# pale_sieve.net
KiCad netlist of a schematic drawn in Altium Designer
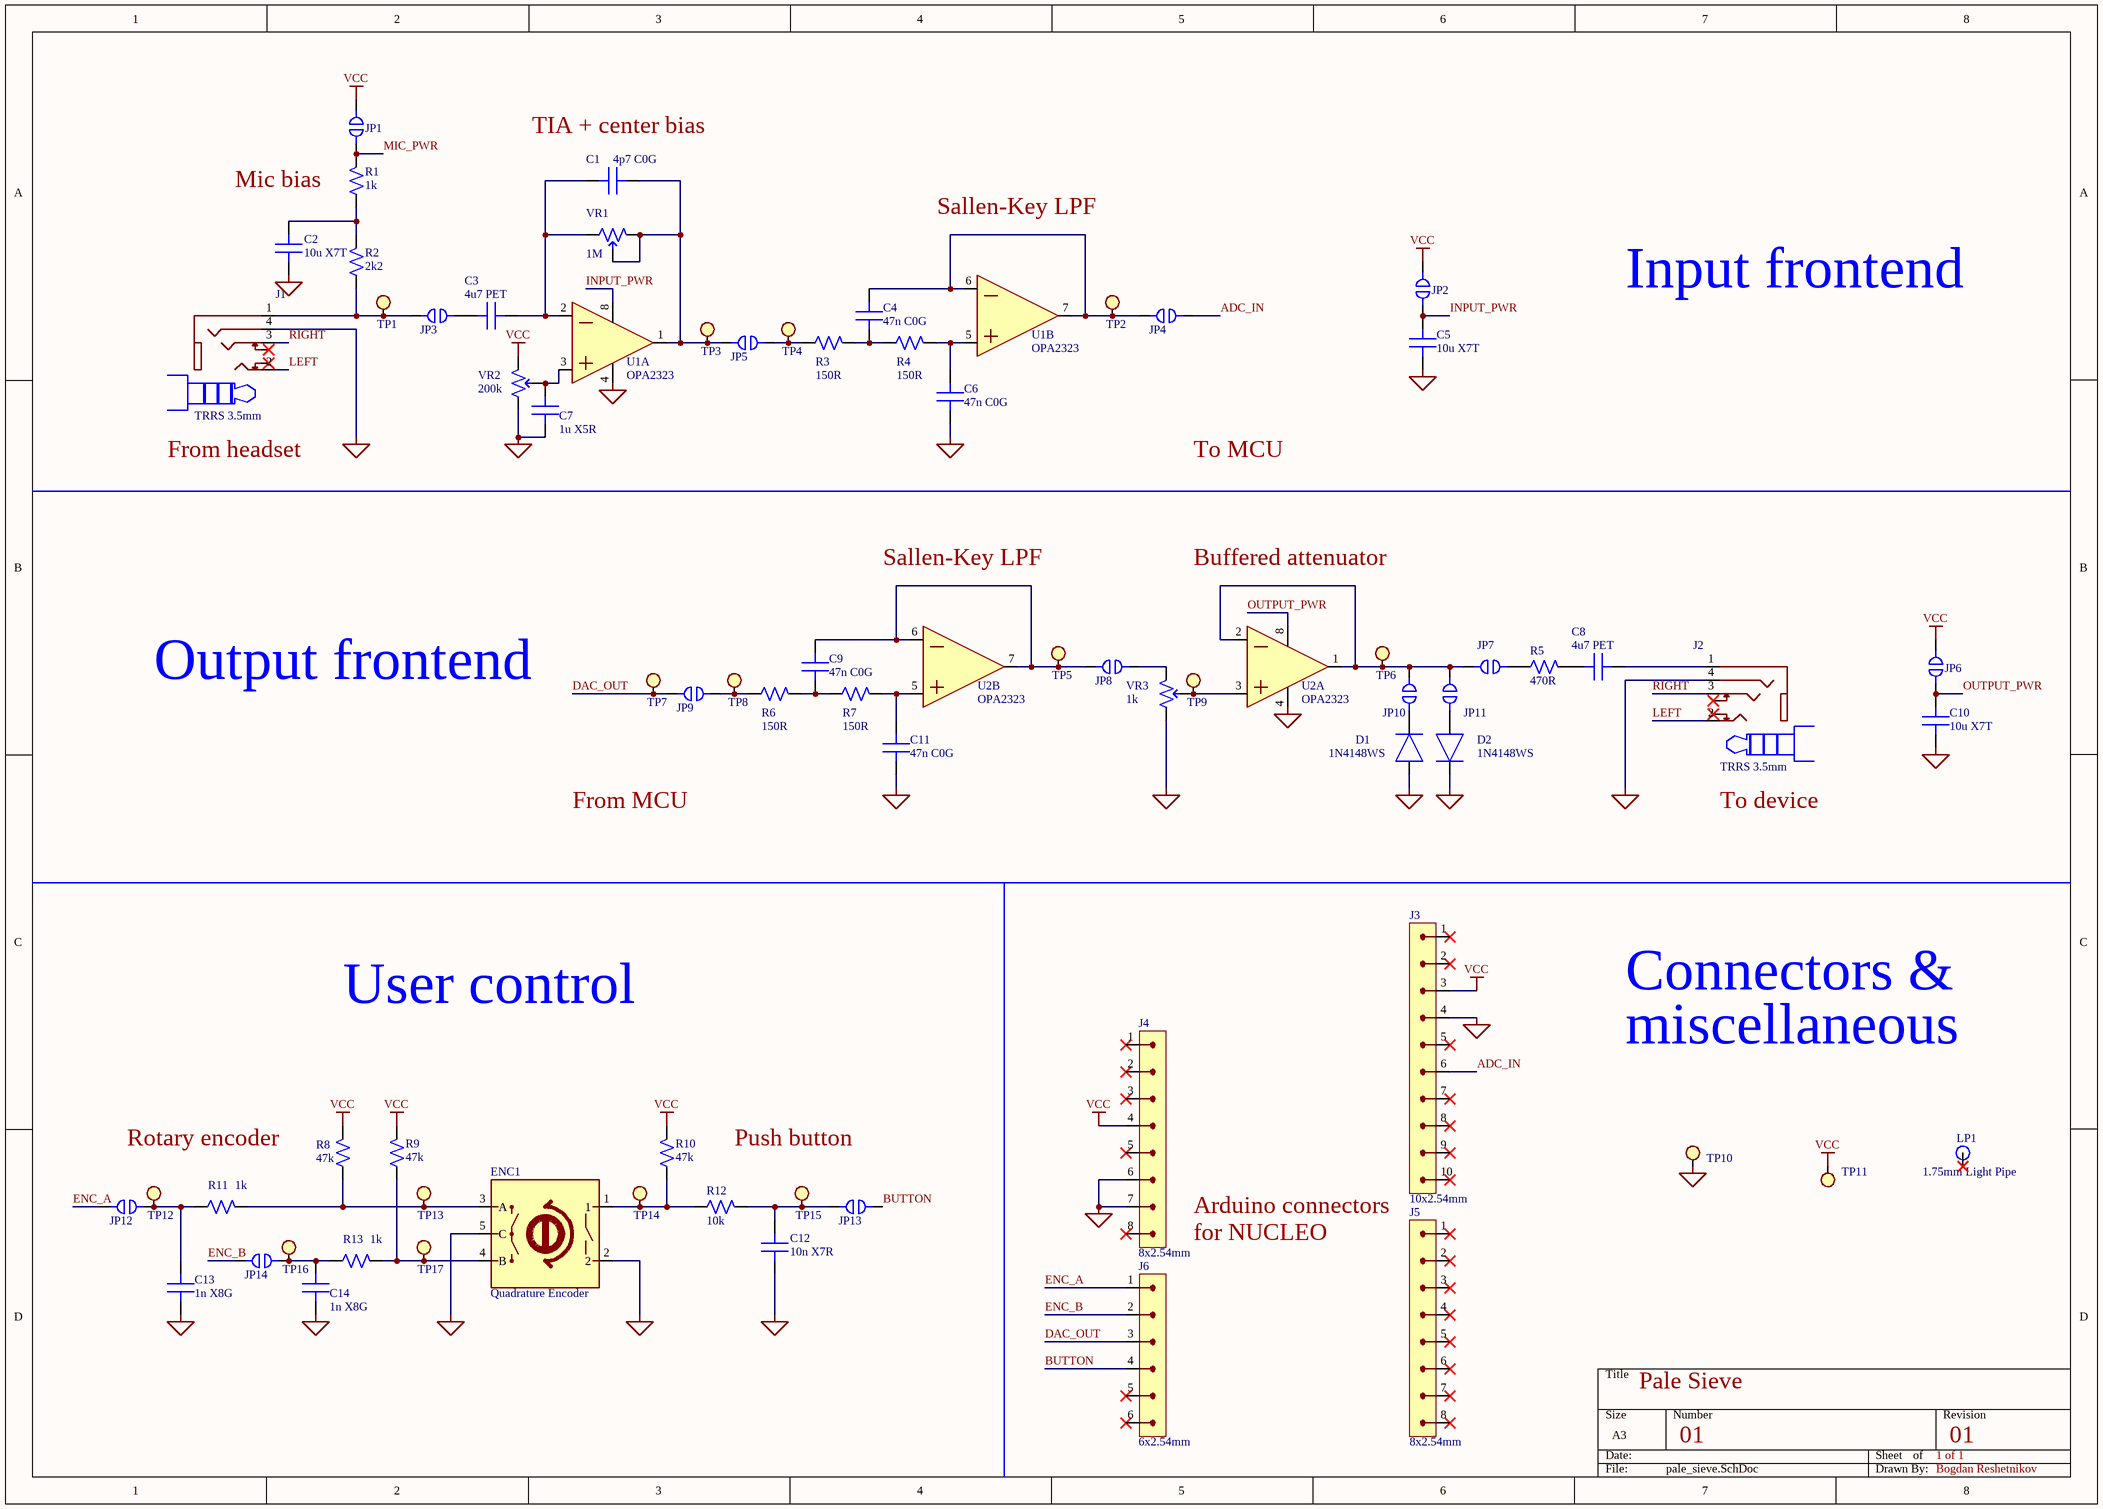
[diagram p0: pale_sieve.SchDoc]

(export (version "E")
  (design (tool "Eeschema 10.0.6"))
  (components
    (comp (ref "C1")
      (value "4p7 C0G")
      (footprint "C0603")
      (description "Multilayer Ceramic Capacitors MLCC - SMD/SMT 50V 4.7pF C0G 0603 5% Tol Ultra Low ESR")
      (fields
        (field (name "MANUFACTURER") "Kyocera AVX")
        (field (name "MANUFACTURER PART NUMBER") "06035U4R7JAT2A")
      )
      (libsource (lib "pale_sieve") (part "06035U4R7JAT2A"))
    )
    (comp (ref "C2")
      (value "10u X7T")
      (footprint "C0603")
      (fields
        (field (name "MANUFACTURER") "TDK")
        (field (name "MANUFACTURER PART NUMBER") "CGA3EDX7T1A106M080AU")
      )
      (libsource (lib "pale_sieve") (part "CGA3EDX7T1A106M080AU"))
    )
    (comp (ref "C3")
      (value "4u7 PET")
      (footprint "6054 WIMA")
      (description "Film Capacitor, Polyethylene Terephthalate, 100V, 10% +Tol, 10% -Tol, 4.7uF, Surface Mount, 6054")
      (fields
        (field (name "MANUFACTURER") "WIMA")
        (field (name "MANUFACTURER PART NUMBER") "SMDTD04470YA00KS00")
      )
      (libsource (lib "pale_sieve") (part "SMDTD04470YA00KS00"))
    )
    (comp (ref "C4")
      (value "47n C0G")
      (footprint "C0805")
      (fields
        (field (name "MANUFACTURER") "KEMET")
        (field (name "MANUFACTURER PART NUMBER") "C0805C473G3GECAUTO")
      )
      (libsource (lib "pale_sieve") (part "C0805C473G3GECAUTO"))
    )
    (comp (ref "C5")
      (value "10u X7T")
      (footprint "C0603")
      (fields
        (field (name "MANUFACTURER") "TDK")
        (field (name "MANUFACTURER PART NUMBER") "CGA3EDX7T1A106M080AU")
      )
      (libsource (lib "pale_sieve") (part "CGA3EDX7T1A106M080AU"))
    )
    (comp (ref "C6")
      (value "47n C0G")
      (footprint "C0805")
      (fields
        (field (name "MANUFACTURER") "KEMET")
        (field (name "MANUFACTURER PART NUMBER") "C0805C473G3GECAUTO")
      )
      (libsource (lib "pale_sieve") (part "C0805C473G3GECAUTO"))
    )
    (comp (ref "C7")
      (value "1u X5R")
      (footprint "C0603")
      (fields
        (field (name "MANUFACTURER") "Kyocera AVX")
        (field (name "MANUFACTURER PART NUMBER") "0603YD105KAT2A")
      )
      (libsource (lib "pale_sieve") (part "0603YD105KAT2A"))
    )
    (comp (ref "C8")
      (value "4u7 PET")
      (footprint "6054 WIMA")
      (description "Film Capacitor, Polyethylene Terephthalate, 100V, 10% +Tol, 10% -Tol, 4.7uF, Surface Mount, 6054")
      (fields
        (field (name "MANUFACTURER") "WIMA")
        (field (name "MANUFACTURER PART NUMBER") "SMDTD04470YA00KS00")
      )
      (libsource (lib "pale_sieve") (part "SMDTD04470YA00KS00"))
    )
    (comp (ref "C9")
      (value "47n C0G")
      (footprint "C0805")
      (fields
        (field (name "MANUFACTURER") "KEMET")
        (field (name "MANUFACTURER PART NUMBER") "C0805C473G3GECAUTO")
      )
      (libsource (lib "pale_sieve") (part "C0805C473G3GECAUTO"))
    )
    (comp (ref "C10")
      (value "10u X7T")
      (footprint "C0603")
      (fields
        (field (name "MANUFACTURER") "TDK")
        (field (name "MANUFACTURER PART NUMBER") "CGA3EDX7T1A106M080AU")
      )
      (libsource (lib "pale_sieve") (part "CGA3EDX7T1A106M080AU"))
    )
    (comp (ref "C11")
      (value "47n C0G")
      (footprint "C0805")
      (fields
        (field (name "MANUFACTURER") "KEMET")
        (field (name "MANUFACTURER PART NUMBER") "C0805C473G3GECAUTO")
      )
      (libsource (lib "pale_sieve") (part "C0805C473G3GECAUTO"))
    )
    (comp (ref "C12")
      (value "10n X7R")
      (footprint "C0603")
      (fields
        (field (name "MANUFACTURER") "Murata")
        (field (name "MANUFACTURER PART NUMBER") "GCM188R71H103KA37J")
      )
      (libsource (lib "pale_sieve") (part "GCM188R71H103KA37J"))
    )
    (comp (ref "C13")
      (value "1n X8G")
      (footprint "C0603")
      (fields
        (field (name "MANUFACTURER") "KEMET")
        (field (name "MANUFACTURER PART NUMBER") "C0603C102J2TACAUTO")
      )
      (libsource (lib "pale_sieve") (part "C0603C102J2TACAUTO"))
    )
    (comp (ref "C14")
      (value "1n X8G")
      (footprint "C0603")
      (fields
        (field (name "MANUFACTURER") "KEMET")
        (field (name "MANUFACTURER PART NUMBER") "C0603C102J2TACAUTO")
      )
      (libsource (lib "pale_sieve") (part "C0603C102J2TACAUTO"))
    )
    (comp (ref "D1")
      (value "1N4148WS")
      (footprint "SOD-323")
      (description "Rectifier Diode, 1 Phase, 1 Element, 0.15A, 100V V(RRM), Silicon")
      (fields (field (name "MANUFACTURER") "ON Semiconductor / Fairchild"))
      (libsource (lib "pale_sieve") (part "1N4148WS"))
    )
    (comp (ref "D2")
      (value "1N4148WS")
      (footprint "SOD-323")
      (description "Rectifier Diode, 1 Phase, 1 Element, 0.15A, 100V V(RRM), Silicon")
      (fields (field (name "MANUFACTURER") "ON Semiconductor / Fairchild"))
      (libsource (lib "pale_sieve") (part "1N4148WS"))
    )
    (comp (ref "ENC1")
      (value "Quadrature Encoder")
      (footprint "PEC11L")
      (description "Rotary Position Encoder")
      (fields
        (field (name "MANUFACTURER") "Bourns")
        (field (name "MANUFACTURER PART NUMBER") "PEC11L-4120F-S0020")
      )
      (libsource (lib "pale_sieve") (part "PEC11L-4120F-S0020"))
    )
    (comp (ref "J1")
      (value "TRRS 3.5mm")
      (footprint "SJ2-35894B-SMT")
      (description "3.5 mm, Stereo, Right Angle, Surface Mount (SMT), Audio Jack Connector")
      (fields
        (field (name "MANUFACTURER") "Same Sky")
        (field (name "MANUFACTURER PART NUMBER") "SJ2-35894B-SMT-TR")
      )
      (libsource (lib "") (part "SJ2-35894B-SMT-TR_1"))
    )
    (comp (ref "J2")
      (value "TRRS 3.5mm")
      (footprint "SJ2-35894B-SMT")
      (description "3.5 mm, Stereo, Right Angle, Surface Mount (SMT), Audio Jack Connector")
      (fields
        (field (name "MANUFACTURER") "Same Sky")
        (field (name "MANUFACTURER PART NUMBER") "SJ2-35894B-SMT-TR")
      )
      (libsource (lib "pale_sieve") (part "SJ2-35894B-SMT-TR"))
    )
    (comp (ref "J3")
      (value "10x2.54mm")
      (footprint "1X10 2.54MM")
      (libsource (lib "pale_sieve") (part "10x2.54mm"))
    )
    (comp (ref "J4") (value "8x2.54mm") (footprint "1x8 2.54MM") (libsource (lib "") (part "8x2.54mm_1")))
    (comp (ref "J5")
      (value "8x2.54mm")
      (footprint "1x8 2.54MM")
      (libsource (lib "pale_sieve") (part "8x2.54mm"))
    )
    (comp (ref "J6")
      (value "6x2.54mm")
      (footprint "1X6 2.54MM")
      (libsource (lib "pale_sieve") (part "6x2.54mm"))
    )
    (comp (ref "JP1")
      (value "Normally open")
      (footprint "SB 1.0x1.5mm")
      (libsource (lib "pale_sieve") (part "SolderBridge"))
    )
    (comp (ref "JP2")
      (value "Normally open")
      (footprint "SB 1.0x1.5mm")
      (libsource (lib "pale_sieve") (part "SolderBridge"))
    )
    (comp (ref "JP3")
      (value "Normally open")
      (footprint "SB 1.0x1.5mm")
      (libsource (lib "pale_sieve") (part "SolderBridge"))
    )
    (comp (ref "JP4")
      (value "Normally open")
      (footprint "SB 1.0x1.5mm")
      (libsource (lib "pale_sieve") (part "SolderBridge"))
    )
    (comp (ref "JP5")
      (value "Normally open")
      (footprint "SB 1.0x1.5mm")
      (libsource (lib "pale_sieve") (part "SolderBridge"))
    )
    (comp (ref "JP6")
      (value "Normally open")
      (footprint "SB 1.0x1.5mm")
      (libsource (lib "pale_sieve") (part "SolderBridge"))
    )
    (comp (ref "JP7")
      (value "Normally open")
      (footprint "SB 1.0x1.5mm")
      (libsource (lib "pale_sieve") (part "SolderBridge"))
    )
    (comp (ref "JP8")
      (value "Normally open")
      (footprint "SB 1.0x1.5mm")
      (libsource (lib "pale_sieve") (part "SolderBridge"))
    )
    (comp (ref "JP9")
      (value "Normally open")
      (footprint "SB 1.0x1.5mm")
      (libsource (lib "pale_sieve") (part "SolderBridge"))
    )
    (comp (ref "JP10")
      (value "Normally open")
      (footprint "SB 1.0x1.5mm")
      (libsource (lib "pale_sieve") (part "SolderBridge"))
    )
    (comp (ref "JP11")
      (value "Normally open")
      (footprint "SB 1.0x1.5mm")
      (libsource (lib "pale_sieve") (part "SolderBridge"))
    )
    (comp (ref "JP12")
      (value "Normally open")
      (footprint "SB 1.0x1.5mm")
      (libsource (lib "pale_sieve") (part "SolderBridge"))
    )
    (comp (ref "JP13")
      (value "Normally open")
      (footprint "SB 1.0x1.5mm")
      (libsource (lib "pale_sieve") (part "SolderBridge"))
    )
    (comp (ref "JP14")
      (value "Normally open")
      (footprint "SB 1.0x1.5mm")
      (libsource (lib "pale_sieve") (part "SolderBridge"))
    )
    (comp (ref "LP1")
      (value "1.75mm Light Pipe")
      (footprint "PTH 1.75MM")
      (libsource (lib "pale_sieve") (part "LightPipe"))
    )
    (comp (ref "R1")
      (value "1k")
      (footprint "R0603")
      (fields
        (field (name "MANUFACTURER") "Vishay")
        (field (name "MANUFACTURER PART NUMBER") "CRCW06031K00FKEI")
        (field (name "TOLERANCE") "1%")
      )
      (libsource (lib "pale_sieve") (part "CRCW06031K00FKEI"))
    )
    (comp (ref "R2")
      (value "2k2")
      (footprint "R0603")
      (fields
        (field (name "MANUFACTURER") "Vishay")
        (field (name "MANUFACTURER PART NUMBER") "CRCW06032K20FKEA")
        (field (name "TOLERANCE") "1%")
      )
      (libsource (lib "pale_sieve") (part "CRCW06032K20FKEA"))
    )
    (comp (ref "R3")
      (value "150R")
      (footprint "R0603")
      (fields
        (field (name "MANUFACTURER") "Vishay")
        (field (name "MANUFACTURER PART NUMBER") "CRCW0603150RFKEA")
        (field (name "TOLERANCE") "1%")
      )
      (libsource (lib "pale_sieve") (part "CRCW0603150RFKEA"))
    )
    (comp (ref "R4")
      (value "150R")
      (footprint "R0603")
      (fields
        (field (name "MANUFACTURER") "Vishay")
        (field (name "MANUFACTURER PART NUMBER") "CRCW0603150RFKEA")
        (field (name "TOLERANCE") "1%")
      )
      (libsource (lib "pale_sieve") (part "CRCW0603150RFKEA"))
    )
    (comp (ref "R5")
      (value "470R")
      (footprint "R0603")
      (fields
        (field (name "MANUFACTURER") "Vishay")
        (field (name "MANUFACTURER PART NUMBER") "CRCW0603470RFKEC")
        (field (name "TOLERANCE") "1%")
      )
      (libsource (lib "pale_sieve") (part "CRCW0603470RFKEC"))
    )
    (comp (ref "R6")
      (value "150R")
      (footprint "R0603")
      (fields
        (field (name "MANUFACTURER") "Vishay")
        (field (name "MANUFACTURER PART NUMBER") "CRCW0603150RFKEA")
        (field (name "TOLERANCE") "1%")
      )
      (libsource (lib "pale_sieve") (part "CRCW0603150RFKEA"))
    )
    (comp (ref "R7")
      (value "150R")
      (footprint "R0603")
      (fields
        (field (name "MANUFACTURER") "Vishay")
        (field (name "MANUFACTURER PART NUMBER") "CRCW0603150RFKEA")
        (field (name "TOLERANCE") "1%")
      )
      (libsource (lib "pale_sieve") (part "CRCW0603150RFKEA"))
    )
    (comp (ref "R8")
      (value "47k")
      (footprint "R0603")
      (fields
        (field (name "MANUFACTURER") "Vishay")
        (field (name "MANUFACTURER PART NUMBER") "CRCW060347K0FKEA")
        (field (name "TOLERANCE") "1%")
      )
      (libsource (lib "pale_sieve") (part "CRCW060347K0FKEA"))
    )
    (comp (ref "R9")
      (value "47k")
      (footprint "R0603")
      (fields
        (field (name "MANUFACTURER") "Vishay")
        (field (name "MANUFACTURER PART NUMBER") "CRCW060347K0FKEA")
        (field (name "TOLERANCE") "1%")
      )
      (libsource (lib "pale_sieve") (part "CRCW060347K0FKEA"))
    )
    (comp (ref "R10")
      (value "47k")
      (footprint "R0603")
      (fields
        (field (name "MANUFACTURER") "Vishay")
        (field (name "MANUFACTURER PART NUMBER") "CRCW060347K0FKEA")
        (field (name "TOLERANCE") "1%")
      )
      (libsource (lib "pale_sieve") (part "CRCW060347K0FKEA"))
    )
    (comp (ref "R11")
      (value "1k")
      (footprint "R0603")
      (fields
        (field (name "MANUFACTURER") "Vishay")
        (field (name "MANUFACTURER PART NUMBER") "CRCW06031K00FKEI")
        (field (name "TOLERANCE") "1%")
      )
      (libsource (lib "pale_sieve") (part "CRCW06031K00FKEI"))
    )
    (comp (ref "R12")
      (value "10k")
      (footprint "R0603")
      (fields
        (field (name "MANUFACTURER") "Vishay")
        (field (name "MANUFACTURER PART NUMBER") "CRCW060310K0FKEA")
        (field (name "TOLERANCE") "1%")
      )
      (libsource (lib "pale_sieve") (part "CRCW060310K0FKEA"))
    )
    (comp (ref "R13")
      (value "1k")
      (footprint "R0603")
      (fields
        (field (name "MANUFACTURER") "Vishay")
        (field (name "MANUFACTURER PART NUMBER") "CRCW06031K00FKEI")
        (field (name "TOLERANCE") "1%")
      )
      (libsource (lib "pale_sieve") (part "CRCW06031K00FKEI"))
    )
    (comp (ref "TP1")
      (value "PTH 0.75mm")
      (footprint "PTH 0.7MM")
      (libsource (lib "pale_sieve") (part "TestPoint"))
    )
    (comp (ref "TP2")
      (value "PTH 0.75mm")
      (footprint "PTH 0.7MM")
      (libsource (lib "pale_sieve") (part "TestPoint"))
    )
    (comp (ref "TP3")
      (value "PTH 0.75mm")
      (footprint "PTH 0.7MM")
      (libsource (lib "pale_sieve") (part "TestPoint"))
    )
    (comp (ref "TP4")
      (value "PTH 0.75mm")
      (footprint "PTH 0.7MM")
      (libsource (lib "pale_sieve") (part "TestPoint"))
    )
    (comp (ref "TP5")
      (value "PTH 0.75mm")
      (footprint "PTH 0.7MM")
      (libsource (lib "pale_sieve") (part "TestPoint"))
    )
    (comp (ref "TP6")
      (value "PTH 0.75mm")
      (footprint "PTH 0.7MM")
      (libsource (lib "pale_sieve") (part "TestPoint"))
    )
    (comp (ref "TP7")
      (value "PTH 0.75mm")
      (footprint "PTH 0.7MM")
      (libsource (lib "pale_sieve") (part "TestPoint"))
    )
    (comp (ref "TP8")
      (value "PTH 0.75mm")
      (footprint "PTH 0.7MM")
      (libsource (lib "pale_sieve") (part "TestPoint"))
    )
    (comp (ref "TP9")
      (value "PTH 0.75mm")
      (footprint "PTH 0.7MM")
      (libsource (lib "pale_sieve") (part "TestPoint"))
    )
    (comp (ref "TP10")
      (value "PTH 0.75mm")
      (footprint "PTH 0.7MM")
      (libsource (lib "pale_sieve") (part "TestPoint"))
    )
    (comp (ref "TP11")
      (value "PTH 0.75mm")
      (footprint "PTH 0.7MM")
      (libsource (lib "pale_sieve") (part "TestPoint"))
    )
    (comp (ref "TP12")
      (value "PTH 0.75mm")
      (footprint "PTH 0.7MM")
      (libsource (lib "pale_sieve") (part "TestPoint"))
    )
    (comp (ref "TP13")
      (value "PTH 0.75mm")
      (footprint "PTH 0.7MM")
      (libsource (lib "pale_sieve") (part "TestPoint"))
    )
    (comp (ref "TP14")
      (value "PTH 0.75mm")
      (footprint "PTH 0.7MM")
      (libsource (lib "pale_sieve") (part "TestPoint"))
    )
    (comp (ref "TP15")
      (value "PTH 0.75mm")
      (footprint "PTH 0.7MM")
      (libsource (lib "pale_sieve") (part "TestPoint"))
    )
    (comp (ref "TP16")
      (value "PTH 0.75mm")
      (footprint "PTH 0.7MM")
      (libsource (lib "pale_sieve") (part "TestPoint"))
    )
    (comp (ref "TP17")
      (value "PTH 0.75mm")
      (footprint "PTH 0.7MM")
      (libsource (lib "pale_sieve") (part "TestPoint"))
    )
    (comp (ref "U1")
      (value "OPA2323")
      (footprint "SOIC-8 D")
      (fields
        (field (name "MANUFACTURER") "Texas Instruments")
        (field (name "MANUFACTURER PART NUMBER") "OPA2323IDR")
      )
      (libsource (lib "pale_sieve") (part "OPA2323IDR"))
    )
    (comp (ref "U2")
      (value "OPA2323")
      (footprint "SOIC-8 D")
      (fields
        (field (name "MANUFACTURER") "Texas Instruments")
        (field (name "MANUFACTURER PART NUMBER") "OPA2323IDR")
      )
      (libsource (lib "pale_sieve") (part "OPA2323IDR"))
    )
    (comp (ref "VR1")
      (value "1M")
      (footprint "TS53YL")
      (description "Trimmer, Cermet, 0.04W, 1000000ohm, 200V, 20% +/-Tol, 100ppm/Cel, 1 Turn(s)")
      (fields
        (field (name "MANUFACTURER") "Vishay Sfernice")
        (field (name "MANUFACTURER PART NUMBER") "TS53YL105MR10")
      )
      (libsource (lib "pale_sieve") (part "TS53YL105MR10"))
    )
    (comp (ref "VR2")
      (value "200k")
      (footprint "TS53YL")
      (description "Trimmer, Cermet, 0.2W, 200000ohm, 200V, 20% +/-Tol, 100ppm/Cel, 1 Turn(s)")
      (fields
        (field (name "MANUFACTURER") "Vishay Sfernice")
        (field (name "MANUFACTURER PART NUMBER") "TS53YL204MR10")
      )
      (libsource (lib "pale_sieve") (part "TS53YL204MR10"))
    )
    (comp (ref "VR3")
      (value "1k")
      (footprint "TS53YL")
      (description "Trimmer, Cermet, 0.25W, 1000ohm, 15.8V, 20% +/-Tol, 100ppm/Cel, 1 Turn(s)")
      (fields
        (field (name "MANUFACTURER") "Vishay")
        (field (name "MANUFACTURER PART NUMBER") "TS53YL102MR10")
      )
      (libsource (lib "pale_sieve") (part "TS53YL102MR10"))
    )
  )
  (nets
    (net (code "1") (name "/ADC_IN") (class "Default")
      (node (ref "J3") (pin "6") (pinfunction "6_6") (pintype "passive"))
      (node (ref "JP4") (pin "2") (pinfunction "2_2") (pintype "passive"))
    )
    (net (code "2") (name "/BUTTON") (class "Default")
      (node (ref "J6") (pin "4") (pinfunction "4_4") (pintype "passive"))
      (node (ref "JP13") (pin "2") (pinfunction "2_2") (pintype "passive"))
    )
    (net (code "3") (name "/DAC_OUT") (class "Default")
      (node (ref "J6") (pin "3") (pinfunction "3_3") (pintype "passive"))
      (node (ref "JP9") (pin "1") (pinfunction "1_1") (pintype "passive"))
      (node (ref "TP7") (pin "1") (pinfunction "1_1") (pintype "passive"))
    )
    (net (code "4") (name "/ENC_A") (class "Default")
      (node (ref "J6") (pin "1") (pinfunction "1_1") (pintype "passive"))
      (node (ref "JP12") (pin "1") (pinfunction "1_1") (pintype "passive"))
    )
    (net (code "5") (name "/ENC_B") (class "Default")
      (node (ref "J6") (pin "2") (pinfunction "2_2") (pintype "passive"))
      (node (ref "JP14") (pin "1") (pinfunction "1_1") (pintype "passive"))
    )
    (net (code "6") (name "/INPUT_PWR") (class "Default")
      (node (ref "C5") (pin "2") (pinfunction "2_2") (pintype "passive"))
      (node (ref "JP2") (pin "1") (pinfunction "1_1") (pintype "passive"))
      (node (ref "U1") (pin "8") (pinfunction "8_8") (pintype "passive"))
    )
    (net (code "7") (name "/LEFT") (class "Default")
      (node (ref "J1") (pin "2") (pinfunction "2_2") (pintype "passive"))
      (node (ref "J2") (pin "2") (pinfunction "2_2") (pintype "passive"))
    )
    (net (code "8") (name "/MIC_PWR") (class "Default")
      (node (ref "JP1") (pin "1") (pinfunction "1_1") (pintype "passive"))
      (node (ref "R1") (pin "2") (pinfunction "2_2") (pintype "passive"))
    )
    (net (code "9") (name "/OUTPUT_PWR") (class "Default")
      (node (ref "C10") (pin "2") (pinfunction "2_2") (pintype "passive"))
      (node (ref "JP6") (pin "1") (pinfunction "1_1") (pintype "passive"))
      (node (ref "U2") (pin "8") (pinfunction "8_8") (pintype "passive"))
    )
    (net (code "10") (name "/RIGHT") (class "Default")
      (node (ref "J1") (pin "3") (pinfunction "3_3") (pintype "passive"))
      (node (ref "J2") (pin "3") (pinfunction "3_3") (pintype "passive"))
    )
    (net (code "11") (name "GND") (class "Default")
      (node (ref "C10") (pin "1") (pinfunction "1_1") (pintype "passive"))
      (node (ref "C11") (pin "1") (pinfunction "1_1") (pintype "passive"))
      (node (ref "C12") (pin "1") (pinfunction "1_1") (pintype "passive"))
      (node (ref "C13") (pin "1") (pinfunction "1_1") (pintype "passive"))
      (node (ref "C14") (pin "1") (pinfunction "1_1") (pintype "passive"))
      (node (ref "C2") (pin "1") (pinfunction "1_1") (pintype "passive"))
      (node (ref "C5") (pin "1") (pinfunction "1_1") (pintype "passive"))
      (node (ref "C6") (pin "1") (pinfunction "1_1") (pintype "passive"))
      (node (ref "C7") (pin "1") (pinfunction "1_1") (pintype "passive"))
      (node (ref "D1") (pin "2") (pinfunction "2_2") (pintype "passive"))
      (node (ref "D2") (pin "1") (pinfunction "1_1") (pintype "passive"))
      (node (ref "ENC1") (pin "2") (pinfunction "2_2") (pintype "passive"))
      (node (ref "ENC1") (pin "5") (pinfunction "C_5") (pintype "passive"))
      (node (ref "J1") (pin "4") (pinfunction "4_4") (pintype "passive"))
      (node (ref "J2") (pin "4") (pinfunction "4_4") (pintype "passive"))
      (node (ref "J3") (pin "4") (pinfunction "4_4") (pintype "passive"))
      (node (ref "J4") (pin "6") (pinfunction "6_6") (pintype "passive"))
      (node (ref "J4") (pin "7") (pinfunction "7_7") (pintype "passive"))
      (node (ref "TP10") (pin "1") (pinfunction "1_1") (pintype "passive"))
      (node (ref "U1") (pin "4") (pinfunction "4_4") (pintype "passive"))
      (node (ref "U2") (pin "4") (pinfunction "4_4") (pintype "passive"))
      (node (ref "VR2") (pin "1") (pinfunction "1_1") (pintype "passive"))
      (node (ref "VR3") (pin "1") (pinfunction "1_1") (pintype "passive"))
    )
    (net (code "12") (name "Net-(C1-Pad1)") (class "Default")
      (node (ref "C1") (pin "1") (pinfunction "1_1") (pintype "passive"))
      (node (ref "C3") (pin "2") (pinfunction "2_2") (pintype "passive"))
      (node (ref "U1") (pin "2") (pinfunction "2_2") (pintype "passive"))
      (node (ref "VR1") (pin "3") (pinfunction "3_3") (pintype "passive"))
    )
    (net (code "13") (name "Net-(C1-Pad2)") (class "Default")
      (node (ref "C1") (pin "2") (pinfunction "2_2") (pintype "passive"))
      (node (ref "JP5") (pin "1") (pinfunction "1_1") (pintype "passive"))
      (node (ref "TP3") (pin "1") (pinfunction "1_1") (pintype "passive"))
      (node (ref "U1") (pin "1") (pinfunction "1_1") (pintype "passive"))
      (node (ref "VR1") (pin "1") (pinfunction "1_1") (pintype "passive"))
      (node (ref "VR1") (pin "2") (pinfunction "2_2") (pintype "passive"))
    )
    (net (code "14") (name "Net-(C2-Pad2)") (class "Default")
      (node (ref "C2") (pin "2") (pinfunction "2_2") (pintype "passive"))
      (node (ref "R1") (pin "1") (pinfunction "1_1") (pintype "passive"))
      (node (ref "R2") (pin "2") (pinfunction "2_2") (pintype "passive"))
    )
    (net (code "15") (name "Net-(C3-Pad1)") (class "Default")
      (node (ref "C3") (pin "1") (pinfunction "1_1") (pintype "passive"))
      (node (ref "JP3") (pin "2") (pinfunction "2_2") (pintype "passive"))
    )
    (net (code "16") (name "Net-(C4-Pad1)") (class "Default")
      (node (ref "C4") (pin "1") (pinfunction "1_1") (pintype "passive"))
      (node (ref "R3") (pin "2") (pinfunction "2_2") (pintype "passive"))
      (node (ref "R4") (pin "1") (pinfunction "1_1") (pintype "passive"))
    )
    (net (code "17") (name "Net-(C4-Pad2)") (class "Default")
      (node (ref "C4") (pin "2") (pinfunction "2_2") (pintype "passive"))
      (node (ref "JP4") (pin "1") (pinfunction "1_1") (pintype "passive"))
      (node (ref "TP2") (pin "1") (pinfunction "1_1") (pintype "passive"))
      (node (ref "U1") (pin "6") (pinfunction "6_6") (pintype "passive"))
      (node (ref "U1") (pin "7") (pinfunction "7_7") (pintype "passive"))
    )
    (net (code "18") (name "Net-(C6-Pad2)") (class "Default")
      (node (ref "C6") (pin "2") (pinfunction "2_2") (pintype "passive"))
      (node (ref "R4") (pin "2") (pinfunction "2_2") (pintype "passive"))
      (node (ref "U1") (pin "5") (pinfunction "5_5") (pintype "passive"))
    )
    (net (code "19") (name "Net-(C7-Pad2)") (class "Default")
      (node (ref "C7") (pin "2") (pinfunction "2_2") (pintype "passive"))
      (node (ref "U1") (pin "3") (pinfunction "3_3") (pintype "passive"))
      (node (ref "VR2") (pin "2") (pinfunction "2_2") (pintype "passive"))
    )
    (net (code "20") (name "Net-(C8-Pad1)") (class "Default")
      (node (ref "C8") (pin "1") (pinfunction "1_1") (pintype "passive"))
      (node (ref "R5") (pin "2") (pinfunction "2_2") (pintype "passive"))
    )
    (net (code "21") (name "Net-(C8-Pad2)") (class "Default")
      (node (ref "C8") (pin "2") (pinfunction "2_2") (pintype "passive"))
      (node (ref "J2") (pin "1") (pinfunction "1_1") (pintype "passive"))
    )
    (net (code "22") (name "Net-(C9-Pad1)") (class "Default")
      (node (ref "C9") (pin "1") (pinfunction "1_1") (pintype "passive"))
      (node (ref "R6") (pin "2") (pinfunction "2_2") (pintype "passive"))
      (node (ref "R7") (pin "1") (pinfunction "1_1") (pintype "passive"))
    )
    (net (code "23") (name "Net-(C9-Pad2)") (class "Default")
      (node (ref "C9") (pin "2") (pinfunction "2_2") (pintype "passive"))
      (node (ref "JP8") (pin "1") (pinfunction "1_1") (pintype "passive"))
      (node (ref "TP5") (pin "1") (pinfunction "1_1") (pintype "passive"))
      (node (ref "U2") (pin "6") (pinfunction "6_6") (pintype "passive"))
      (node (ref "U2") (pin "7") (pinfunction "7_7") (pintype "passive"))
    )
    (net (code "24") (name "Net-(C11-Pad2)") (class "Default")
      (node (ref "C11") (pin "2") (pinfunction "2_2") (pintype "passive"))
      (node (ref "R7") (pin "2") (pinfunction "2_2") (pintype "passive"))
      (node (ref "U2") (pin "5") (pinfunction "5_5") (pintype "passive"))
    )
    (net (code "25") (name "Net-(C12-Pad2)") (class "Default")
      (node (ref "C12") (pin "2") (pinfunction "2_2") (pintype "passive"))
      (node (ref "JP13") (pin "1") (pinfunction "1_1") (pintype "passive"))
      (node (ref "R12") (pin "2") (pinfunction "2_2") (pintype "passive"))
      (node (ref "TP15") (pin "1") (pinfunction "1_1") (pintype "passive"))
    )
    (net (code "26") (name "Net-(C13-Pad2)") (class "Default")
      (node (ref "C13") (pin "2") (pinfunction "2_2") (pintype "passive"))
      (node (ref "JP12") (pin "2") (pinfunction "2_2") (pintype "passive"))
      (node (ref "R11") (pin "1") (pinfunction "1_1") (pintype "passive"))
      (node (ref "TP12") (pin "1") (pinfunction "1_1") (pintype "passive"))
    )
    (net (code "27") (name "Net-(C14-Pad2)") (class "Default")
      (node (ref "C14") (pin "2") (pinfunction "2_2") (pintype "passive"))
      (node (ref "JP14") (pin "2") (pinfunction "2_2") (pintype "passive"))
      (node (ref "R13") (pin "1") (pinfunction "1_1") (pintype "passive"))
      (node (ref "TP16") (pin "1") (pinfunction "1_1") (pintype "passive"))
    )
    (net (code "28") (name "Net-(D1-Pad1)") (class "Default")
      (node (ref "D1") (pin "1") (pinfunction "1_1") (pintype "passive"))
      (node (ref "JP10") (pin "1") (pinfunction "1_1") (pintype "passive"))
    )
    (net (code "29") (name "Net-(D2-Pad2)") (class "Default")
      (node (ref "D2") (pin "2") (pinfunction "2_2") (pintype "passive"))
      (node (ref "JP11") (pin "1") (pinfunction "1_1") (pintype "passive"))
    )
    (net (code "30") (name "Net-(ENC1-A)") (class "Default")
      (node (ref "ENC1") (pin "3") (pinfunction "A_3") (pintype "passive"))
      (node (ref "R11") (pin "2") (pinfunction "2_2") (pintype "passive"))
      (node (ref "R8") (pin "1") (pinfunction "1_1") (pintype "passive"))
      (node (ref "TP13") (pin "1") (pinfunction "1_1") (pintype "passive"))
    )
    (net (code "31") (name "Net-(ENC1-B)") (class "Default")
      (node (ref "ENC1") (pin "4") (pinfunction "B_4") (pintype "passive"))
      (node (ref "R13") (pin "2") (pinfunction "2_2") (pintype "passive"))
      (node (ref "R9") (pin "1") (pinfunction "1_1") (pintype "passive"))
      (node (ref "TP17") (pin "1") (pinfunction "1_1") (pintype "passive"))
    )
    (net (code "32") (name "Net-(ENC1-Pad1)") (class "Default")
      (node (ref "ENC1") (pin "1") (pinfunction "1_1") (pintype "passive"))
      (node (ref "R10") (pin "1") (pinfunction "1_1") (pintype "passive"))
      (node (ref "R12") (pin "1") (pinfunction "1_1") (pintype "passive"))
      (node (ref "TP14") (pin "1") (pinfunction "1_1") (pintype "passive"))
    )
    (net (code "33") (name "Net-(J1-Pad1)") (class "Default")
      (node (ref "J1") (pin "1") (pinfunction "1_1") (pintype "passive"))
      (node (ref "JP3") (pin "1") (pinfunction "1_1") (pintype "passive"))
      (node (ref "R2") (pin "1") (pinfunction "1_1") (pintype "passive"))
      (node (ref "TP1") (pin "1") (pinfunction "1_1") (pintype "passive"))
    )
    (net (code "34") (name "Net-(JP5-Pad2)") (class "Default")
      (node (ref "JP5") (pin "2") (pinfunction "2_2") (pintype "passive"))
      (node (ref "R3") (pin "1") (pinfunction "1_1") (pintype "passive"))
      (node (ref "TP4") (pin "1") (pinfunction "1_1") (pintype "passive"))
    )
    (net (code "35") (name "Net-(JP7-Pad2)") (class "Default")
      (node (ref "JP7") (pin "2") (pinfunction "2_2") (pintype "passive"))
      (node (ref "R5") (pin "1") (pinfunction "1_1") (pintype "passive"))
    )
    (net (code "36") (name "Net-(JP8-Pad2)") (class "Default")
      (node (ref "JP8") (pin "2") (pinfunction "2_2") (pintype "passive"))
      (node (ref "VR3") (pin "3") (pinfunction "3_3") (pintype "passive"))
    )
    (net (code "37") (name "Net-(JP9-Pad2)") (class "Default")
      (node (ref "JP9") (pin "2") (pinfunction "2_2") (pintype "passive"))
      (node (ref "R6") (pin "1") (pinfunction "1_1") (pintype "passive"))
      (node (ref "TP8") (pin "1") (pinfunction "1_1") (pintype "passive"))
    )
    (net (code "38") (name "Net-(JP10-Pad2)") (class "Default")
      (node (ref "JP10") (pin "2") (pinfunction "2_2") (pintype "passive"))
      (node (ref "JP11") (pin "2") (pinfunction "2_2") (pintype "passive"))
      (node (ref "JP7") (pin "1") (pinfunction "1_1") (pintype "passive"))
      (node (ref "TP6") (pin "1") (pinfunction "1_1") (pintype "passive"))
      (node (ref "U2") (pin "1") (pinfunction "1_1") (pintype "passive"))
      (node (ref "U2") (pin "2") (pinfunction "2_2") (pintype "passive"))
    )
    (net (code "39") (name "Net-(TP9-Pad1)") (class "Default")
      (node (ref "TP9") (pin "1") (pinfunction "1_1") (pintype "passive"))
      (node (ref "U2") (pin "3") (pinfunction "3_3") (pintype "passive"))
      (node (ref "VR3") (pin "2") (pinfunction "2_2") (pintype "passive"))
    )
    (net (code "40") (name "VCC") (class "Default")
      (node (ref "J3") (pin "3") (pinfunction "3_3") (pintype "passive"))
      (node (ref "J4") (pin "4") (pinfunction "4_4") (pintype "passive"))
      (node (ref "JP1") (pin "2") (pinfunction "2_2") (pintype "passive"))
      (node (ref "JP2") (pin "2") (pinfunction "2_2") (pintype "passive"))
      (node (ref "JP6") (pin "2") (pinfunction "2_2") (pintype "passive"))
      (node (ref "R10") (pin "2") (pinfunction "2_2") (pintype "passive"))
      (node (ref "R8") (pin "2") (pinfunction "2_2") (pintype "passive"))
      (node (ref "R9") (pin "2") (pinfunction "2_2") (pintype "passive"))
      (node (ref "TP11") (pin "1") (pinfunction "1_1") (pintype "passive"))
      (node (ref "VR2") (pin "3") (pinfunction "3_3") (pintype "passive"))
    )
    (net (code "41") (name "unconnected-(J1-Pad10)") (class "Default")
      (node (ref "J1") (pin "10") (pinfunction "10_10") (pintype "passive+no_connect"))
    )
    (net (code "42") (name "unconnected-(J1-Pad11)") (class "Default")
      (node (ref "J1") (pin "11") (pinfunction "11_11") (pintype "passive+no_connect"))
    )
    (net (code "43") (name "unconnected-(J2-Pad10)") (class "Default")
      (node (ref "J2") (pin "10") (pinfunction "10_10") (pintype "passive+no_connect"))
    )
    (net (code "44") (name "unconnected-(J2-Pad11)") (class "Default")
      (node (ref "J2") (pin "11") (pinfunction "11_11") (pintype "passive+no_connect"))
    )
    (net (code "45") (name "unconnected-(J3-Pad1)") (class "Default")
      (node (ref "J3") (pin "1") (pinfunction "1_1") (pintype "passive+no_connect"))
    )
    (net (code "46") (name "unconnected-(J3-Pad2)") (class "Default")
      (node (ref "J3") (pin "2") (pinfunction "2_2") (pintype "passive+no_connect"))
    )
    (net (code "47") (name "unconnected-(J3-Pad5)") (class "Default")
      (node (ref "J3") (pin "5") (pinfunction "5_5") (pintype "passive+no_connect"))
    )
    (net (code "48") (name "unconnected-(J3-Pad7)") (class "Default")
      (node (ref "J3") (pin "7") (pinfunction "7_7") (pintype "passive+no_connect"))
    )
    (net (code "49") (name "unconnected-(J3-Pad8)") (class "Default")
      (node (ref "J3") (pin "8") (pinfunction "8_8") (pintype "passive+no_connect"))
    )
    (net (code "50") (name "unconnected-(J3-Pad9)") (class "Default")
      (node (ref "J3") (pin "9") (pinfunction "9_9") (pintype "passive+no_connect"))
    )
    (net (code "51") (name "unconnected-(J3-Pad10)") (class "Default")
      (node (ref "J3") (pin "10") (pinfunction "10_10") (pintype "passive+no_connect"))
    )
    (net (code "52") (name "unconnected-(J4-Pad1)") (class "Default")
      (node (ref "J4") (pin "1") (pinfunction "1_1") (pintype "passive+no_connect"))
    )
    (net (code "53") (name "unconnected-(J4-Pad2)") (class "Default")
      (node (ref "J4") (pin "2") (pinfunction "2_2") (pintype "passive+no_connect"))
    )
    (net (code "54") (name "unconnected-(J4-Pad3)") (class "Default")
      (node (ref "J4") (pin "3") (pinfunction "3_3") (pintype "passive+no_connect"))
    )
    (net (code "55") (name "unconnected-(J4-Pad5)") (class "Default")
      (node (ref "J4") (pin "5") (pinfunction "5_5") (pintype "passive+no_connect"))
    )
    (net (code "56") (name "unconnected-(J4-Pad8)") (class "Default")
      (node (ref "J4") (pin "8") (pinfunction "8_8") (pintype "passive+no_connect"))
    )
    (net (code "57") (name "unconnected-(J5-Pad1)") (class "Default")
      (node (ref "J5") (pin "1") (pinfunction "1_1") (pintype "passive+no_connect"))
    )
    (net (code "58") (name "unconnected-(J5-Pad2)") (class "Default")
      (node (ref "J5") (pin "2") (pinfunction "2_2") (pintype "passive+no_connect"))
    )
    (net (code "59") (name "unconnected-(J5-Pad3)") (class "Default")
      (node (ref "J5") (pin "3") (pinfunction "3_3") (pintype "passive+no_connect"))
    )
    (net (code "60") (name "unconnected-(J5-Pad4)") (class "Default")
      (node (ref "J5") (pin "4") (pinfunction "4_4") (pintype "passive+no_connect"))
    )
    (net (code "61") (name "unconnected-(J5-Pad5)") (class "Default")
      (node (ref "J5") (pin "5") (pinfunction "5_5") (pintype "passive+no_connect"))
    )
    (net (code "62") (name "unconnected-(J5-Pad6)") (class "Default")
      (node (ref "J5") (pin "6") (pinfunction "6_6") (pintype "passive+no_connect"))
    )
    (net (code "63") (name "unconnected-(J5-Pad7)") (class "Default")
      (node (ref "J5") (pin "7") (pinfunction "7_7") (pintype "passive+no_connect"))
    )
    (net (code "64") (name "unconnected-(J5-Pad8)") (class "Default")
      (node (ref "J5") (pin "8") (pinfunction "8_8") (pintype "passive+no_connect"))
    )
    (net (code "65") (name "unconnected-(J6-Pad5)") (class "Default")
      (node (ref "J6") (pin "5") (pinfunction "5_5") (pintype "passive+no_connect"))
    )
    (net (code "66") (name "unconnected-(J6-Pad6)") (class "Default")
      (node (ref "J6") (pin "6") (pinfunction "6_6") (pintype "passive+no_connect"))
    )
    (net (code "67") (name "unconnected-(LP1-Pad1)") (class "Default")
      (node (ref "LP1") (pin "1") (pinfunction "1_1") (pintype "passive+no_connect"))
    )
  )
)
